# 13-I225_2.net
KiCad netlist of a schematic drawn in Altium Designer
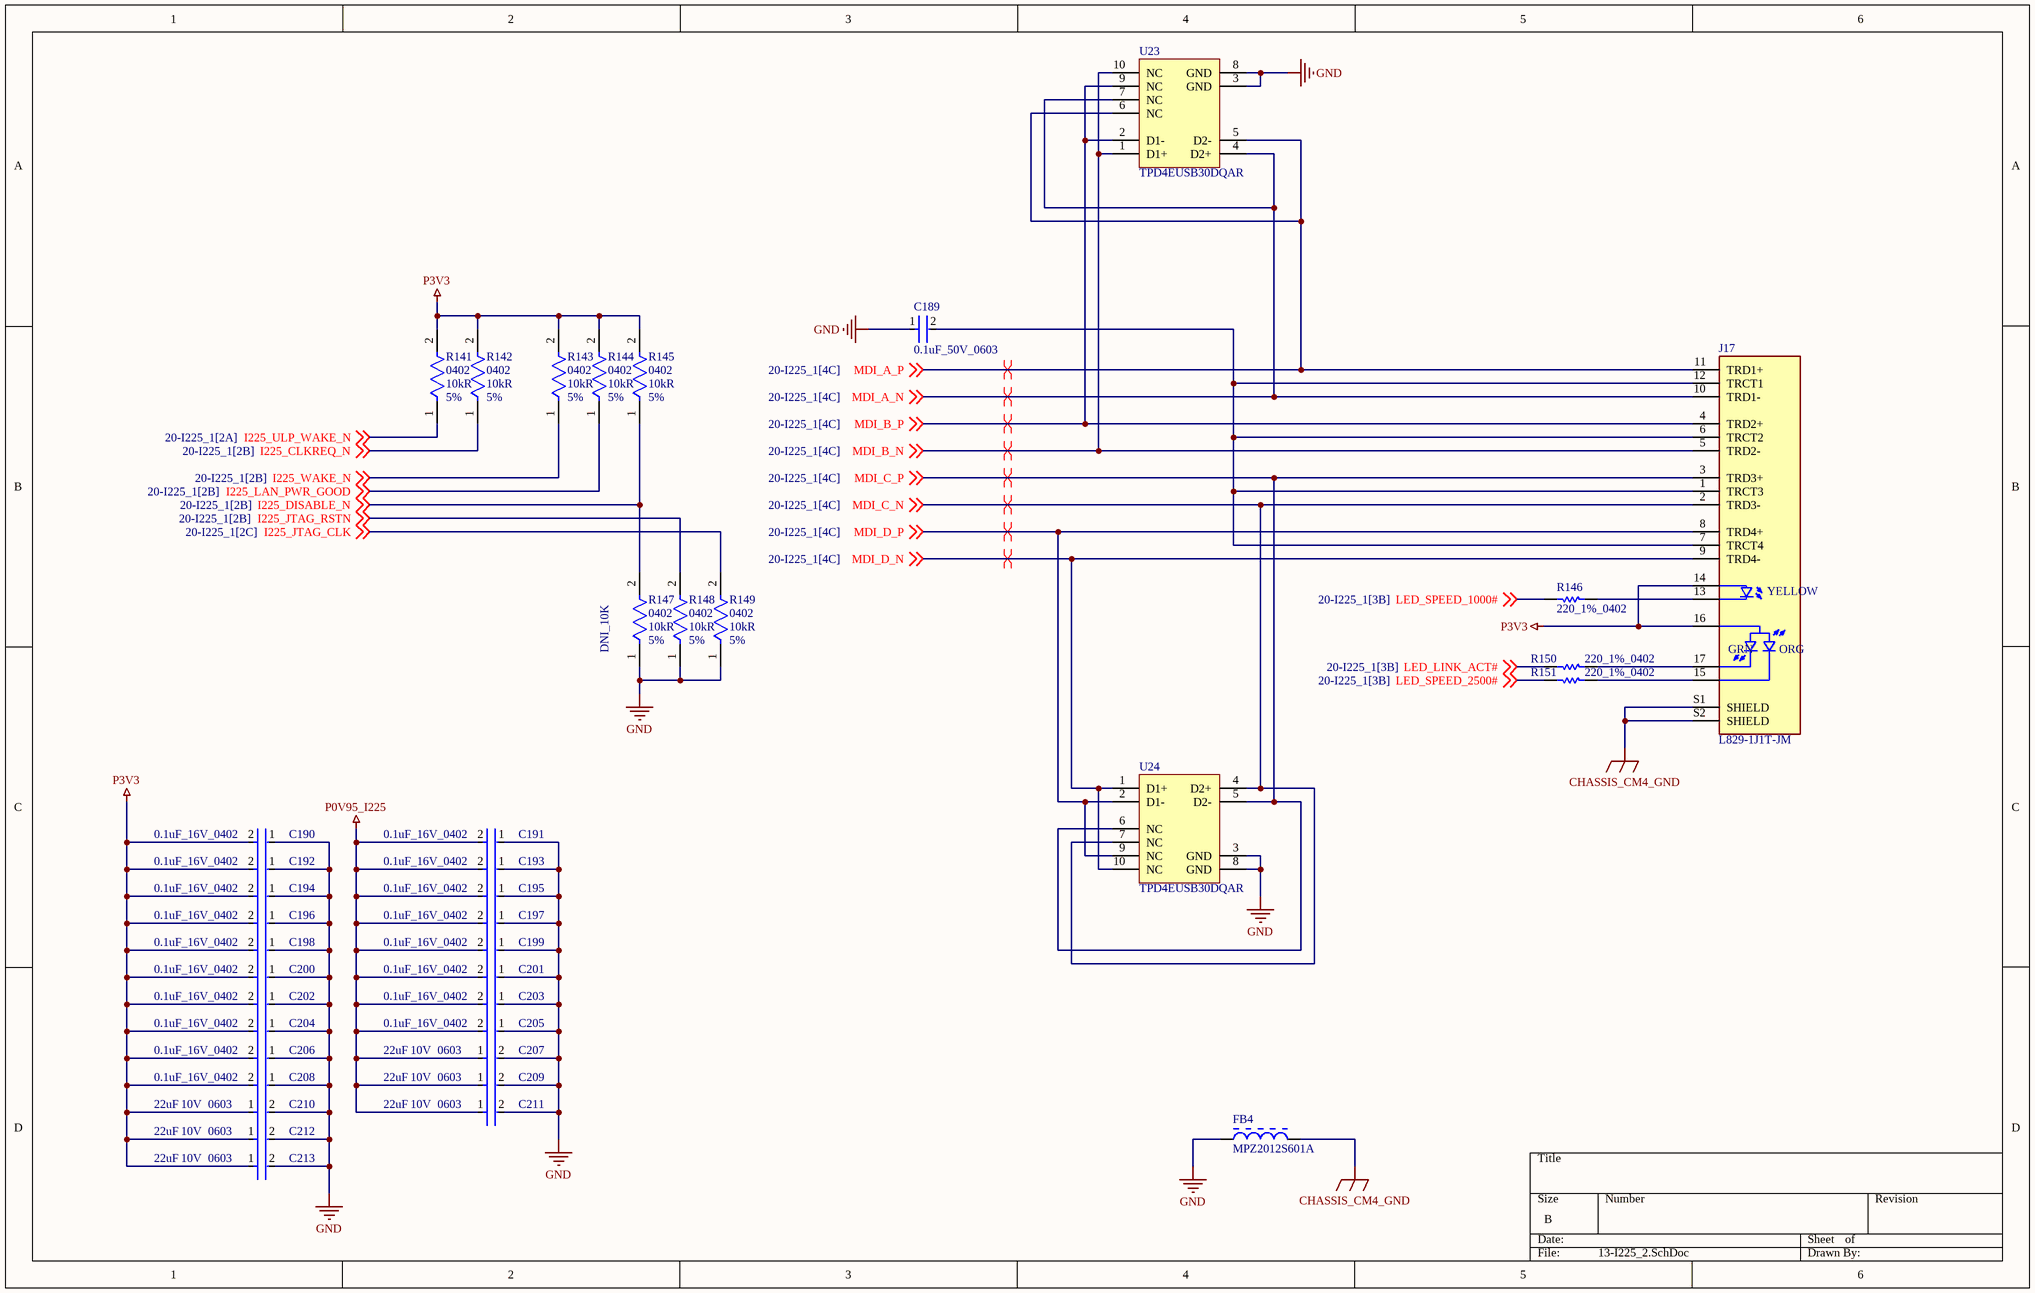
[diagram p0: 13-I225_2.SchDoc]

(export (version "E")
  (design (tool "Eeschema 10.0.6"))
  (components
    (comp (ref "C189")
      (value "0.1uF_50V_0603")
      (footprint "FP-C0603-CJ-MFG")
      (description "CAP CER 0.1UF 50V X7R 0603")
      (fields (field (name "MANUFACTURER PART NUMBER") "C0603X104K5RACTU") (field (name "VOLTAGE") "50V"))
      (libsource (lib "Altium Content Vault") (part "11868f565c42a9108669ba33697ecf6"))
    )
    (comp (ref "C190")
      (value "0.1uF_16V_0402")
      (footprint "FP-GRM15-MFG")
      (description "CAP CER 0.1UF 16V X7R 0402")
      (fields (field (name "MANUFACTURER PART NUMBER") "GRM155R71C104KA88D") (field (name "TOLERANCE") "10%"))
      (libsource (lib "Altium Content Vault") (part "236180d848d6139a670b325ea6854c9"))
    )
    (comp (ref "C191")
      (value "0.1uF_16V_0402")
      (footprint "FP-GRM15-MFG")
      (description "CAP CER 0.1UF 16V X7R 0402")
      (fields (field (name "MANUFACTURER PART NUMBER") "GRM155R71C104KA88D") (field (name "TOLERANCE") "10%"))
      (libsource (lib "Altium Content Vault") (part "236180d848d6139a670b325ea6854c9"))
    )
    (comp (ref "C192")
      (value "0.1uF_16V_0402")
      (footprint "FP-GRM15-MFG")
      (description "CAP CER 0.1UF 16V X7R 0402")
      (fields (field (name "MANUFACTURER PART NUMBER") "GRM155R71C104KA88D") (field (name "TOLERANCE") "10%"))
      (libsource (lib "Altium Content Vault") (part "236180d848d6139a670b325ea6854c9"))
    )
    (comp (ref "C193")
      (value "0.1uF_16V_0402")
      (footprint "FP-GRM15-MFG")
      (description "CAP CER 0.1UF 16V X7R 0402")
      (fields (field (name "MANUFACTURER PART NUMBER") "GRM155R71C104KA88D") (field (name "TOLERANCE") "10%"))
      (libsource (lib "Altium Content Vault") (part "236180d848d6139a670b325ea6854c9"))
    )
    (comp (ref "C194")
      (value "0.1uF_16V_0402")
      (footprint "FP-GRM15-MFG")
      (description "CAP CER 0.1UF 16V X7R 0402")
      (fields (field (name "MANUFACTURER PART NUMBER") "GRM155R71C104KA88D") (field (name "TOLERANCE") "10%"))
      (libsource (lib "Altium Content Vault") (part "236180d848d6139a670b325ea6854c9"))
    )
    (comp (ref "C195")
      (value "0.1uF_16V_0402")
      (footprint "FP-GRM15-MFG")
      (description "CAP CER 0.1UF 16V X7R 0402")
      (fields (field (name "MANUFACTURER PART NUMBER") "GRM155R71C104KA88D") (field (name "TOLERANCE") "10%"))
      (libsource (lib "Altium Content Vault") (part "236180d848d6139a670b325ea6854c9"))
    )
    (comp (ref "C196")
      (value "0.1uF_16V_0402")
      (footprint "FP-GRM15-MFG")
      (description "CAP CER 0.1UF 16V X7R 0402")
      (fields (field (name "MANUFACTURER PART NUMBER") "GRM155R71C104KA88D") (field (name "TOLERANCE") "10%"))
      (libsource (lib "Altium Content Vault") (part "236180d848d6139a670b325ea6854c9"))
    )
    (comp (ref "C197")
      (value "0.1uF_16V_0402")
      (footprint "FP-GRM15-MFG")
      (description "CAP CER 0.1UF 16V X7R 0402")
      (fields (field (name "MANUFACTURER PART NUMBER") "GRM155R71C104KA88D") (field (name "TOLERANCE") "10%"))
      (libsource (lib "Altium Content Vault") (part "236180d848d6139a670b325ea6854c9"))
    )
    (comp (ref "C198")
      (value "0.1uF_16V_0402")
      (footprint "FP-GRM15-MFG")
      (description "CAP CER 0.1UF 16V X7R 0402")
      (fields (field (name "MANUFACTURER PART NUMBER") "GRM155R71C104KA88D") (field (name "TOLERANCE") "10%"))
      (libsource (lib "Altium Content Vault") (part "236180d848d6139a670b325ea6854c9"))
    )
    (comp (ref "C199")
      (value "0.1uF_16V_0402")
      (footprint "FP-GRM15-MFG")
      (description "CAP CER 0.1UF 16V X7R 0402")
      (fields (field (name "MANUFACTURER PART NUMBER") "GRM155R71C104KA88D") (field (name "TOLERANCE") "10%"))
      (libsource (lib "Altium Content Vault") (part "236180d848d6139a670b325ea6854c9"))
    )
    (comp (ref "C200")
      (value "0.1uF_16V_0402")
      (footprint "FP-GRM15-MFG")
      (description "CAP CER 0.1UF 16V X7R 0402")
      (fields (field (name "MANUFACTURER PART NUMBER") "GRM155R71C104KA88D") (field (name "TOLERANCE") "10%"))
      (libsource (lib "Altium Content Vault") (part "236180d848d6139a670b325ea6854c9"))
    )
    (comp (ref "C201")
      (value "0.1uF_16V_0402")
      (footprint "FP-GRM15-MFG")
      (description "CAP CER 0.1UF 16V X7R 0402")
      (fields (field (name "MANUFACTURER PART NUMBER") "GRM155R71C104KA88D") (field (name "TOLERANCE") "10%"))
      (libsource (lib "Altium Content Vault") (part "236180d848d6139a670b325ea6854c9"))
    )
    (comp (ref "C202")
      (value "0.1uF_16V_0402")
      (footprint "FP-GRM15-MFG")
      (description "CAP CER 0.1UF 16V X7R 0402")
      (fields (field (name "MANUFACTURER PART NUMBER") "GRM155R71C104KA88D") (field (name "TOLERANCE") "10%"))
      (libsource (lib "Altium Content Vault") (part "236180d848d6139a670b325ea6854c9"))
    )
    (comp (ref "C203")
      (value "0.1uF_16V_0402")
      (footprint "FP-GRM15-MFG")
      (description "CAP CER 0.1UF 16V X7R 0402")
      (fields (field (name "MANUFACTURER PART NUMBER") "GRM155R71C104KA88D") (field (name "TOLERANCE") "10%"))
      (libsource (lib "Altium Content Vault") (part "236180d848d6139a670b325ea6854c9"))
    )
    (comp (ref "C204")
      (value "0.1uF_16V_0402")
      (footprint "FP-GRM15-MFG")
      (description "CAP CER 0.1UF 16V X7R 0402")
      (fields (field (name "MANUFACTURER PART NUMBER") "GRM155R71C104KA88D") (field (name "TOLERANCE") "10%"))
      (libsource (lib "Altium Content Vault") (part "236180d848d6139a670b325ea6854c9"))
    )
    (comp (ref "C205")
      (value "0.1uF_16V_0402")
      (footprint "FP-GRM15-MFG")
      (description "CAP CER 0.1UF 16V X7R 0402")
      (fields (field (name "MANUFACTURER PART NUMBER") "GRM155R71C104KA88D") (field (name "TOLERANCE") "10%"))
      (libsource (lib "Altium Content Vault") (part "236180d848d6139a670b325ea6854c9"))
    )
    (comp (ref "C206")
      (value "0.1uF_16V_0402")
      (footprint "FP-GRM15-MFG")
      (description "CAP CER 0.1UF 16V X7R 0402")
      (fields (field (name "MANUFACTURER PART NUMBER") "GRM155R71C104KA88D") (field (name "TOLERANCE") "10%"))
      (libsource (lib "Altium Content Vault") (part "236180d848d6139a670b325ea6854c9"))
    )
    (comp (ref "C207")
      (value "GRM188R61A226ME15D")
      (footprint "FP-GRM188-0_2-IPC_C")
      (description "Chip Multilayer Ceramic Capacitors for General Purpose, 0603, 22uF, X5R, 15%, 20%, 10V")
      (fields
        (field (name "TOLERANCE") "20%")
        (field (name "CAPACITANCE") "22uF")
        (field (name "VOLTAGE RATING") "10V")
        (field (name "CASE CODE (IMPERIAL)") "0603")
      )
      (libsource (lib "Altium Content Vault") (part "11868f565c42a9108669ba33697ecf6"))
    )
    (comp (ref "C208")
      (value "0.1uF_16V_0402")
      (footprint "FP-GRM15-MFG")
      (description "CAP CER 0.1UF 16V X7R 0402")
      (fields (field (name "MANUFACTURER PART NUMBER") "GRM155R71C104KA88D") (field (name "TOLERANCE") "10%"))
      (libsource (lib "Altium Content Vault") (part "236180d848d6139a670b325ea6854c9"))
    )
    (comp (ref "C209")
      (value "GRM188R61A226ME15D")
      (footprint "FP-GRM188-0_2-IPC_C")
      (description "Chip Multilayer Ceramic Capacitors for General Purpose, 0603, 22uF, X5R, 15%, 20%, 10V")
      (fields
        (field (name "TOLERANCE") "20%")
        (field (name "CAPACITANCE") "22uF")
        (field (name "VOLTAGE RATING") "10V")
        (field (name "CASE CODE (IMPERIAL)") "0603")
      )
      (libsource (lib "Altium Content Vault") (part "11868f565c42a9108669ba33697ecf6"))
    )
    (comp (ref "C210")
      (value "GRM188R61A226ME15D")
      (footprint "FP-GRM188-0_2-IPC_C")
      (description "Chip Multilayer Ceramic Capacitors for General Purpose, 0603, 22uF, X5R, 15%, 20%, 10V")
      (fields
        (field (name "TOLERANCE") "20%")
        (field (name "CAPACITANCE") "22uF")
        (field (name "VOLTAGE RATING") "10V")
        (field (name "CASE CODE (IMPERIAL)") "0603")
      )
      (libsource (lib "Altium Content Vault") (part "11868f565c42a9108669ba33697ecf6"))
    )
    (comp (ref "C211")
      (value "GRM188R61A226ME15D")
      (footprint "FP-GRM188-0_2-IPC_C")
      (description "Chip Multilayer Ceramic Capacitors for General Purpose, 0603, 22uF, X5R, 15%, 20%, 10V")
      (fields
        (field (name "TOLERANCE") "20%")
        (field (name "CAPACITANCE") "22uF")
        (field (name "VOLTAGE RATING") "10V")
        (field (name "CASE CODE (IMPERIAL)") "0603")
      )
      (libsource (lib "Altium Content Vault") (part "11868f565c42a9108669ba33697ecf6"))
    )
    (comp (ref "C212")
      (value "GRM188R61A226ME15D")
      (footprint "FP-GRM188-0_2-IPC_C")
      (description "Chip Multilayer Ceramic Capacitors for General Purpose, 0603, 22uF, X5R, 15%, 20%, 10V")
      (fields
        (field (name "TOLERANCE") "20%")
        (field (name "CAPACITANCE") "22uF")
        (field (name "VOLTAGE RATING") "10V")
        (field (name "CASE CODE (IMPERIAL)") "0603")
      )
      (libsource (lib "Altium Content Vault") (part "11868f565c42a9108669ba33697ecf6"))
    )
    (comp (ref "C213")
      (value "GRM188R61A226ME15D")
      (footprint "FP-GRM188-0_2-IPC_C")
      (description "Chip Multilayer Ceramic Capacitors for General Purpose, 0603, 22uF, X5R, 15%, 20%, 10V")
      (fields
        (field (name "TOLERANCE") "20%")
        (field (name "CAPACITANCE") "22uF")
        (field (name "VOLTAGE RATING") "10V")
        (field (name "CASE CODE (IMPERIAL)") "0603")
      )
      (libsource (lib "Altium Content Vault") (part "11868f565c42a9108669ba33697ecf6"))
    )
    (comp (ref "FB4")
      (value "MPZ2012S601A")
      (footprint "TDK-MPZ2012_V")
      (fields (field (name "TOLERANCE") "25%") (field (name "MANUFACTURER") "TDK"))
      (libsource (lib "Altium Content Vault") (part "BEAD-2"))
    )
    (comp (ref "J17")
      (value "L829-1J1T-JM")
      (footprint "BEL_L829-1J1T-JM")
      (description "MagJack 2.5GBASE-T ¦ 1X1 ¦ OG/Y LED ¦ -40 to 85C ¦ RoHS")
      (fields
        (field (name "DIGI-KEY_PART_NUMBER") "507-2068-ND")
        (field (name "MF") "Bel Magnetic Solutions")
      )
      (libsource (lib "SnapEDAsch") (part "L829-1J1T-JM"))
    )
    (comp (ref "R141")
      (value "CRCW040210K0JNED")
      (footprint "FP-CRCW0402-e3-IPC_B")
      (description "RES Thick Film, 10kΩ, 5%, 0.063W, 200ppm/°C, 0402")
      (fields
        (field (name "CASE/PACKAGE") "0402")
        (field (name "RESISTANCE") "10kR")
        (field (name "TOLERANCE") "5%")
      )
      (libsource (lib "Altium Content Vault") (part "1029c3af85768c4190bb7ad29bc67b5"))
    )
    (comp (ref "R142")
      (value "CRCW040210K0JNED")
      (footprint "FP-CRCW0402-e3-IPC_B")
      (description "RES Thick Film, 10kΩ, 5%, 0.063W, 200ppm/°C, 0402")
      (fields
        (field (name "CASE/PACKAGE") "0402")
        (field (name "RESISTANCE") "10kR")
        (field (name "TOLERANCE") "5%")
      )
      (libsource (lib "Altium Content Vault") (part "1029c3af85768c4190bb7ad29bc67b5"))
    )
    (comp (ref "R143")
      (value "CRCW040210K0JNED")
      (footprint "FP-CRCW0402-e3-IPC_B")
      (description "RES Thick Film, 10kΩ, 5%, 0.063W, 200ppm/°C, 0402")
      (fields
        (field (name "CASE/PACKAGE") "0402")
        (field (name "RESISTANCE") "10kR")
        (field (name "TOLERANCE") "5%")
      )
      (libsource (lib "Altium Content Vault") (part "1029c3af85768c4190bb7ad29bc67b5"))
    )
    (comp (ref "R144")
      (value "CRCW040210K0JNED")
      (footprint "FP-CRCW0402-e3-IPC_B")
      (description "RES Thick Film, 10kΩ, 5%, 0.063W, 200ppm/°C, 0402")
      (fields
        (field (name "CASE/PACKAGE") "0402")
        (field (name "RESISTANCE") "10kR")
        (field (name "TOLERANCE") "5%")
      )
      (libsource (lib "Altium Content Vault") (part "1029c3af85768c4190bb7ad29bc67b5"))
    )
    (comp (ref "R145")
      (value "CRCW040210K0JNED")
      (footprint "FP-CRCW0402-e3-IPC_B")
      (description "RES Thick Film, 10kΩ, 5%, 0.063W, 200ppm/°C, 0402")
      (fields
        (field (name "CASE/PACKAGE") "0402")
        (field (name "RESISTANCE") "10kR")
        (field (name "TOLERANCE") "5%")
      )
      (libsource (lib "Altium Content Vault") (part "1029c3af85768c4190bb7ad29bc67b5"))
    )
    (comp (ref "R146")
      (value "220_1%_0402")
      (footprint "RESC1005X40X25LL10T10")
      (fields (field (name "PART NUMBER") "RK73H1ETTP2200F") (field (name "MANUFACTURER") "KOA Speer"))
      (libsource (lib "Altium Content Vault") (part "RES"))
    )
    (comp (ref "R147")
      (value "DNI_10K")
      (footprint "FP-CRCW0402-e3-IPC_B")
      (description "RES Thick Film, 10kΩ, 5%, 0.063W, 200ppm/°C, 0402")
      (fields
        (field (name "CASE/PACKAGE") "0402")
        (field (name "RESISTANCE") "10kR")
        (field (name "TOLERANCE") "5%")
      )
      (libsource (lib "Altium Content Vault") (part "1029c3af85768c4190bb7ad29bc67b5"))
    )
    (comp (ref "R148")
      (value "CRCW040210K0JNED")
      (footprint "FP-CRCW0402-e3-IPC_B")
      (description "RES Thick Film, 10kΩ, 5%, 0.063W, 200ppm/°C, 0402")
      (fields
        (field (name "CASE/PACKAGE") "0402")
        (field (name "RESISTANCE") "10kR")
        (field (name "TOLERANCE") "5%")
      )
      (libsource (lib "Altium Content Vault") (part "1029c3af85768c4190bb7ad29bc67b5"))
    )
    (comp (ref "R149")
      (value "CRCW040210K0JNED")
      (footprint "FP-CRCW0402-e3-IPC_B")
      (description "RES Thick Film, 10kΩ, 5%, 0.063W, 200ppm/°C, 0402")
      (fields
        (field (name "CASE/PACKAGE") "0402")
        (field (name "RESISTANCE") "10kR")
        (field (name "TOLERANCE") "5%")
      )
      (libsource (lib "Altium Content Vault") (part "1029c3af85768c4190bb7ad29bc67b5"))
    )
    (comp (ref "R150")
      (value "220_1%_0402")
      (footprint "RESC1005X40X25LL10T10")
      (fields (field (name "PART NUMBER") "RK73H1ETTP2200F") (field (name "MANUFACTURER") "KOA Speer"))
      (libsource (lib "Altium Content Vault") (part "RES"))
    )
    (comp (ref "R151")
      (value "220_1%_0402")
      (footprint "RESC1005X40X25LL10T10")
      (fields (field (name "PART NUMBER") "RK73H1ETTP2200F") (field (name "MANUFACTURER") "KOA Speer"))
      (libsource (lib "Altium Content Vault") (part "RES"))
    )
    (comp (ref "U23")
      (value "TPD4EUSB30DQAR")
      (footprint "DQA0010A_V")
      (fields (field (name "MANUFACTURER") "Texas Instruments"))
      (libsource (lib "Altium Content Vault") (part "TI-TPD4EUSB30-SON_DQA-10"))
    )
    (comp (ref "U24")
      (value "TPD4EUSB30DQAR")
      (footprint "DQA0010A_V")
      (fields (field (name "MANUFACTURER") "Texas Instruments"))
      (libsource (lib "") (part "TI-TPD4EUSB30-SON_DQA-10_1"))
    )
  )
  (nets
    (net (code "1") (name "CHASSIS_CM4_GND") (class "Default")
      (node (ref "FB4") (pin "2") (pinfunction "2_2") (pintype "passive"))
      (node (ref "J17") (pin "S1") (pinfunction "SHIELD_S1") (pintype "passive"))
      (node (ref "J17") (pin "S2") (pinfunction "SHIELD_S2") (pintype "passive"))
    )
    (net (code "2") (name "GND") (class "Default")
      (node (ref "C189") (pin "1") (pinfunction "1_1") (pintype "passive"))
      (node (ref "C190") (pin "1") (pinfunction "1_1") (pintype "passive"))
      (node (ref "C191") (pin "1") (pinfunction "1_1") (pintype "passive"))
      (node (ref "C192") (pin "1") (pinfunction "1_1") (pintype "passive"))
      (node (ref "C193") (pin "1") (pinfunction "1_1") (pintype "passive"))
      (node (ref "C194") (pin "1") (pinfunction "1_1") (pintype "passive"))
      (node (ref "C195") (pin "1") (pinfunction "1_1") (pintype "passive"))
      (node (ref "C196") (pin "1") (pinfunction "1_1") (pintype "passive"))
      (node (ref "C197") (pin "1") (pinfunction "1_1") (pintype "passive"))
      (node (ref "C198") (pin "1") (pinfunction "1_1") (pintype "passive"))
      (node (ref "C199") (pin "1") (pinfunction "1_1") (pintype "passive"))
      (node (ref "C200") (pin "1") (pinfunction "1_1") (pintype "passive"))
      (node (ref "C201") (pin "1") (pinfunction "1_1") (pintype "passive"))
      (node (ref "C202") (pin "1") (pinfunction "1_1") (pintype "passive"))
      (node (ref "C203") (pin "1") (pinfunction "1_1") (pintype "passive"))
      (node (ref "C204") (pin "1") (pinfunction "1_1") (pintype "passive"))
      (node (ref "C205") (pin "1") (pinfunction "1_1") (pintype "passive"))
      (node (ref "C206") (pin "1") (pinfunction "1_1") (pintype "passive"))
      (node (ref "C207") (pin "2") (pinfunction "2_2") (pintype "passive"))
      (node (ref "C208") (pin "1") (pinfunction "1_1") (pintype "passive"))
      (node (ref "C209") (pin "2") (pinfunction "2_2") (pintype "passive"))
      (node (ref "C210") (pin "2") (pinfunction "2_2") (pintype "passive"))
      (node (ref "C211") (pin "2") (pinfunction "2_2") (pintype "passive"))
      (node (ref "C212") (pin "2") (pinfunction "2_2") (pintype "passive"))
      (node (ref "C213") (pin "2") (pinfunction "2_2") (pintype "passive"))
      (node (ref "FB4") (pin "1") (pinfunction "1_1") (pintype "passive"))
      (node (ref "R147") (pin "1") (pinfunction "1_1") (pintype "passive"))
      (node (ref "R148") (pin "1") (pinfunction "1_1") (pintype "passive"))
      (node (ref "R149") (pin "1") (pinfunction "1_1") (pintype "passive"))
      (node (ref "U23") (pin "3") (pinfunction "GND_3") (pintype "power_in"))
      (node (ref "U23") (pin "8") (pinfunction "GND_8") (pintype "power_in"))
      (node (ref "U24") (pin "3") (pinfunction "GND_3") (pintype "power_in"))
      (node (ref "U24") (pin "8") (pinfunction "GND_8") (pintype "power_in"))
    )
    (net (code "3") (name "I225_CLKREQ_N") (class "Default")
      (node (ref "R142") (pin "1") (pinfunction "1_1") (pintype "passive"))
    )
    (net (code "4") (name "I225_DISABLE_N") (class "Default")
      (node (ref "R145") (pin "1") (pinfunction "1_1") (pintype "passive"))
      (node (ref "R147") (pin "2") (pinfunction "2_2") (pintype "passive"))
    )
    (net (code "5") (name "I225_JTAG_CLK") (class "Default")
      (node (ref "R149") (pin "2") (pinfunction "2_2") (pintype "passive"))
    )
    (net (code "6") (name "I225_JTAG_RSTN") (class "Default")
      (node (ref "R148") (pin "2") (pinfunction "2_2") (pintype "passive"))
    )
    (net (code "7") (name "I225_LAN_PWR_GOOD") (class "Default")
      (node (ref "R144") (pin "1") (pinfunction "1_1") (pintype "passive"))
    )
    (net (code "8") (name "I225_ULP_WAKE_N") (class "Default")
      (node (ref "R141") (pin "1") (pinfunction "1_1") (pintype "passive"))
    )
    (net (code "9") (name "I225_WAKE_N") (class "Default")
      (node (ref "R143") (pin "1") (pinfunction "1_1") (pintype "passive"))
    )
    (net (code "10") (name "LED_LINK_ACT#") (class "Default")
      (node (ref "R150") (pin "2") (pinfunction "2_2") (pintype "passive"))
    )
    (net (code "11") (name "LED_SPEED_1000#") (class "Default")
      (node (ref "R146") (pin "2") (pinfunction "2_2") (pintype "passive"))
    )
    (net (code "12") (name "LED_SPEED_2500#") (class "Default")
      (node (ref "R151") (pin "2") (pinfunction "2_2") (pintype "passive"))
    )
    (net (code "13") (name "MDI_A_N") (class "Default")
      (node (ref "J17") (pin "10") (pinfunction "TRD1-_10") (pintype "passive"))
      (node (ref "U23") (pin "4") (pinfunction "D2+_4") (pintype "passive"))
      (node (ref "U23") (pin "7") (pinfunction "NC_7") (pintype "passive"))
    )
    (net (code "14") (name "MDI_A_P") (class "Default")
      (node (ref "J17") (pin "11") (pinfunction "TRD1+_11") (pintype "passive"))
      (node (ref "U23") (pin "5") (pinfunction "D2-_5") (pintype "passive"))
      (node (ref "U23") (pin "6") (pinfunction "NC_6") (pintype "passive"))
    )
    (net (code "15") (name "MDI_B_N") (class "Default")
      (node (ref "J17") (pin "5") (pinfunction "TRD2-_5") (pintype "passive"))
      (node (ref "U23") (pin "1") (pinfunction "D1+_1") (pintype "passive"))
      (node (ref "U23") (pin "10") (pinfunction "NC_10") (pintype "passive"))
    )
    (net (code "16") (name "MDI_B_P") (class "Default")
      (node (ref "J17") (pin "4") (pinfunction "TRD2+_4") (pintype "passive"))
      (node (ref "U23") (pin "2") (pinfunction "D1-_2") (pintype "passive"))
      (node (ref "U23") (pin "9") (pinfunction "NC_9") (pintype "passive"))
    )
    (net (code "17") (name "MDI_C_N") (class "Default")
      (node (ref "J17") (pin "2") (pinfunction "TRD3-_2") (pintype "passive"))
      (node (ref "U24") (pin "4") (pinfunction "D2+_4") (pintype "passive"))
      (node (ref "U24") (pin "7") (pinfunction "NC_7") (pintype "passive"))
    )
    (net (code "18") (name "MDI_C_P") (class "Default")
      (node (ref "J17") (pin "3") (pinfunction "TRD3+_3") (pintype "passive"))
      (node (ref "U24") (pin "5") (pinfunction "D2-_5") (pintype "passive"))
      (node (ref "U24") (pin "6") (pinfunction "NC_6") (pintype "passive"))
    )
    (net (code "19") (name "MDI_D_N") (class "Default")
      (node (ref "J17") (pin "9") (pinfunction "TRD4-_9") (pintype "passive"))
      (node (ref "U24") (pin "1") (pinfunction "D1+_1") (pintype "passive"))
      (node (ref "U24") (pin "10") (pinfunction "NC_10") (pintype "passive"))
    )
    (net (code "20") (name "MDI_D_P") (class "Default")
      (node (ref "J17") (pin "8") (pinfunction "TRD4+_8") (pintype "passive"))
      (node (ref "U24") (pin "2") (pinfunction "D1-_2") (pintype "passive"))
      (node (ref "U24") (pin "9") (pinfunction "NC_9") (pintype "passive"))
    )
    (net (code "21") (name "Net-(J17-GK_1)") (class "Default")
      (node (ref "J17") (pin "17") (pinfunction "GK_1_17") (pintype "passive"))
      (node (ref "R150") (pin "1") (pinfunction "1_1") (pintype "passive"))
    )
    (net (code "22") (name "Net-(J17-OK_1)") (class "Default")
      (node (ref "J17") (pin "15") (pinfunction "OK_1_15") (pintype "passive"))
      (node (ref "R151") (pin "1") (pinfunction "1_1") (pintype "passive"))
    )
    (net (code "23") (name "Net-(J17-TRCT1)") (class "Default")
      (node (ref "C189") (pin "2") (pinfunction "2_2") (pintype "passive"))
      (node (ref "J17") (pin "1") (pinfunction "TRCT3_1") (pintype "passive"))
      (node (ref "J17") (pin "12") (pinfunction "TRCT1_12") (pintype "passive"))
      (node (ref "J17") (pin "6") (pinfunction "TRCT2_6") (pintype "passive"))
      (node (ref "J17") (pin "7") (pinfunction "TRCT4_7") (pintype "passive"))
    )
    (net (code "24") (name "Net-(J17-YK_1)") (class "Default")
      (node (ref "J17") (pin "13") (pinfunction "YK_1_13") (pintype "passive"))
      (node (ref "R146") (pin "1") (pinfunction "1_1") (pintype "passive"))
    )
    (net (code "25") (name "P0V95_I225") (class "Default")
      (node (ref "C191") (pin "2") (pinfunction "2_2") (pintype "passive"))
      (node (ref "C193") (pin "2") (pinfunction "2_2") (pintype "passive"))
      (node (ref "C195") (pin "2") (pinfunction "2_2") (pintype "passive"))
      (node (ref "C197") (pin "2") (pinfunction "2_2") (pintype "passive"))
      (node (ref "C199") (pin "2") (pinfunction "2_2") (pintype "passive"))
      (node (ref "C201") (pin "2") (pinfunction "2_2") (pintype "passive"))
      (node (ref "C203") (pin "2") (pinfunction "2_2") (pintype "passive"))
      (node (ref "C205") (pin "2") (pinfunction "2_2") (pintype "passive"))
      (node (ref "C207") (pin "1") (pinfunction "1_1") (pintype "passive"))
      (node (ref "C209") (pin "1") (pinfunction "1_1") (pintype "passive"))
      (node (ref "C211") (pin "1") (pinfunction "1_1") (pintype "passive"))
    )
    (net (code "26") (name "P3V3") (class "Default")
      (node (ref "C190") (pin "2") (pinfunction "2_2") (pintype "passive"))
      (node (ref "C192") (pin "2") (pinfunction "2_2") (pintype "passive"))
      (node (ref "C194") (pin "2") (pinfunction "2_2") (pintype "passive"))
      (node (ref "C196") (pin "2") (pinfunction "2_2") (pintype "passive"))
      (node (ref "C198") (pin "2") (pinfunction "2_2") (pintype "passive"))
      (node (ref "C200") (pin "2") (pinfunction "2_2") (pintype "passive"))
      (node (ref "C202") (pin "2") (pinfunction "2_2") (pintype "passive"))
      (node (ref "C204") (pin "2") (pinfunction "2_2") (pintype "passive"))
      (node (ref "C206") (pin "2") (pinfunction "2_2") (pintype "passive"))
      (node (ref "C208") (pin "2") (pinfunction "2_2") (pintype "passive"))
      (node (ref "C210") (pin "1") (pinfunction "1_1") (pintype "passive"))
      (node (ref "C212") (pin "1") (pinfunction "1_1") (pintype "passive"))
      (node (ref "C213") (pin "1") (pinfunction "1_1") (pintype "passive"))
      (node (ref "J17") (pin "14") (pinfunction "YA_1_14") (pintype "passive"))
      (node (ref "J17") (pin "16") (pinfunction "CA_16") (pintype "passive"))
      (node (ref "R141") (pin "2") (pinfunction "2_2") (pintype "passive"))
      (node (ref "R142") (pin "2") (pinfunction "2_2") (pintype "passive"))
      (node (ref "R143") (pin "2") (pinfunction "2_2") (pintype "passive"))
      (node (ref "R144") (pin "2") (pinfunction "2_2") (pintype "passive"))
      (node (ref "R145") (pin "2") (pinfunction "2_2") (pintype "passive"))
    )
  )
)
